# Control.net
KiCad netlist of a schematic drawn in EAGLE
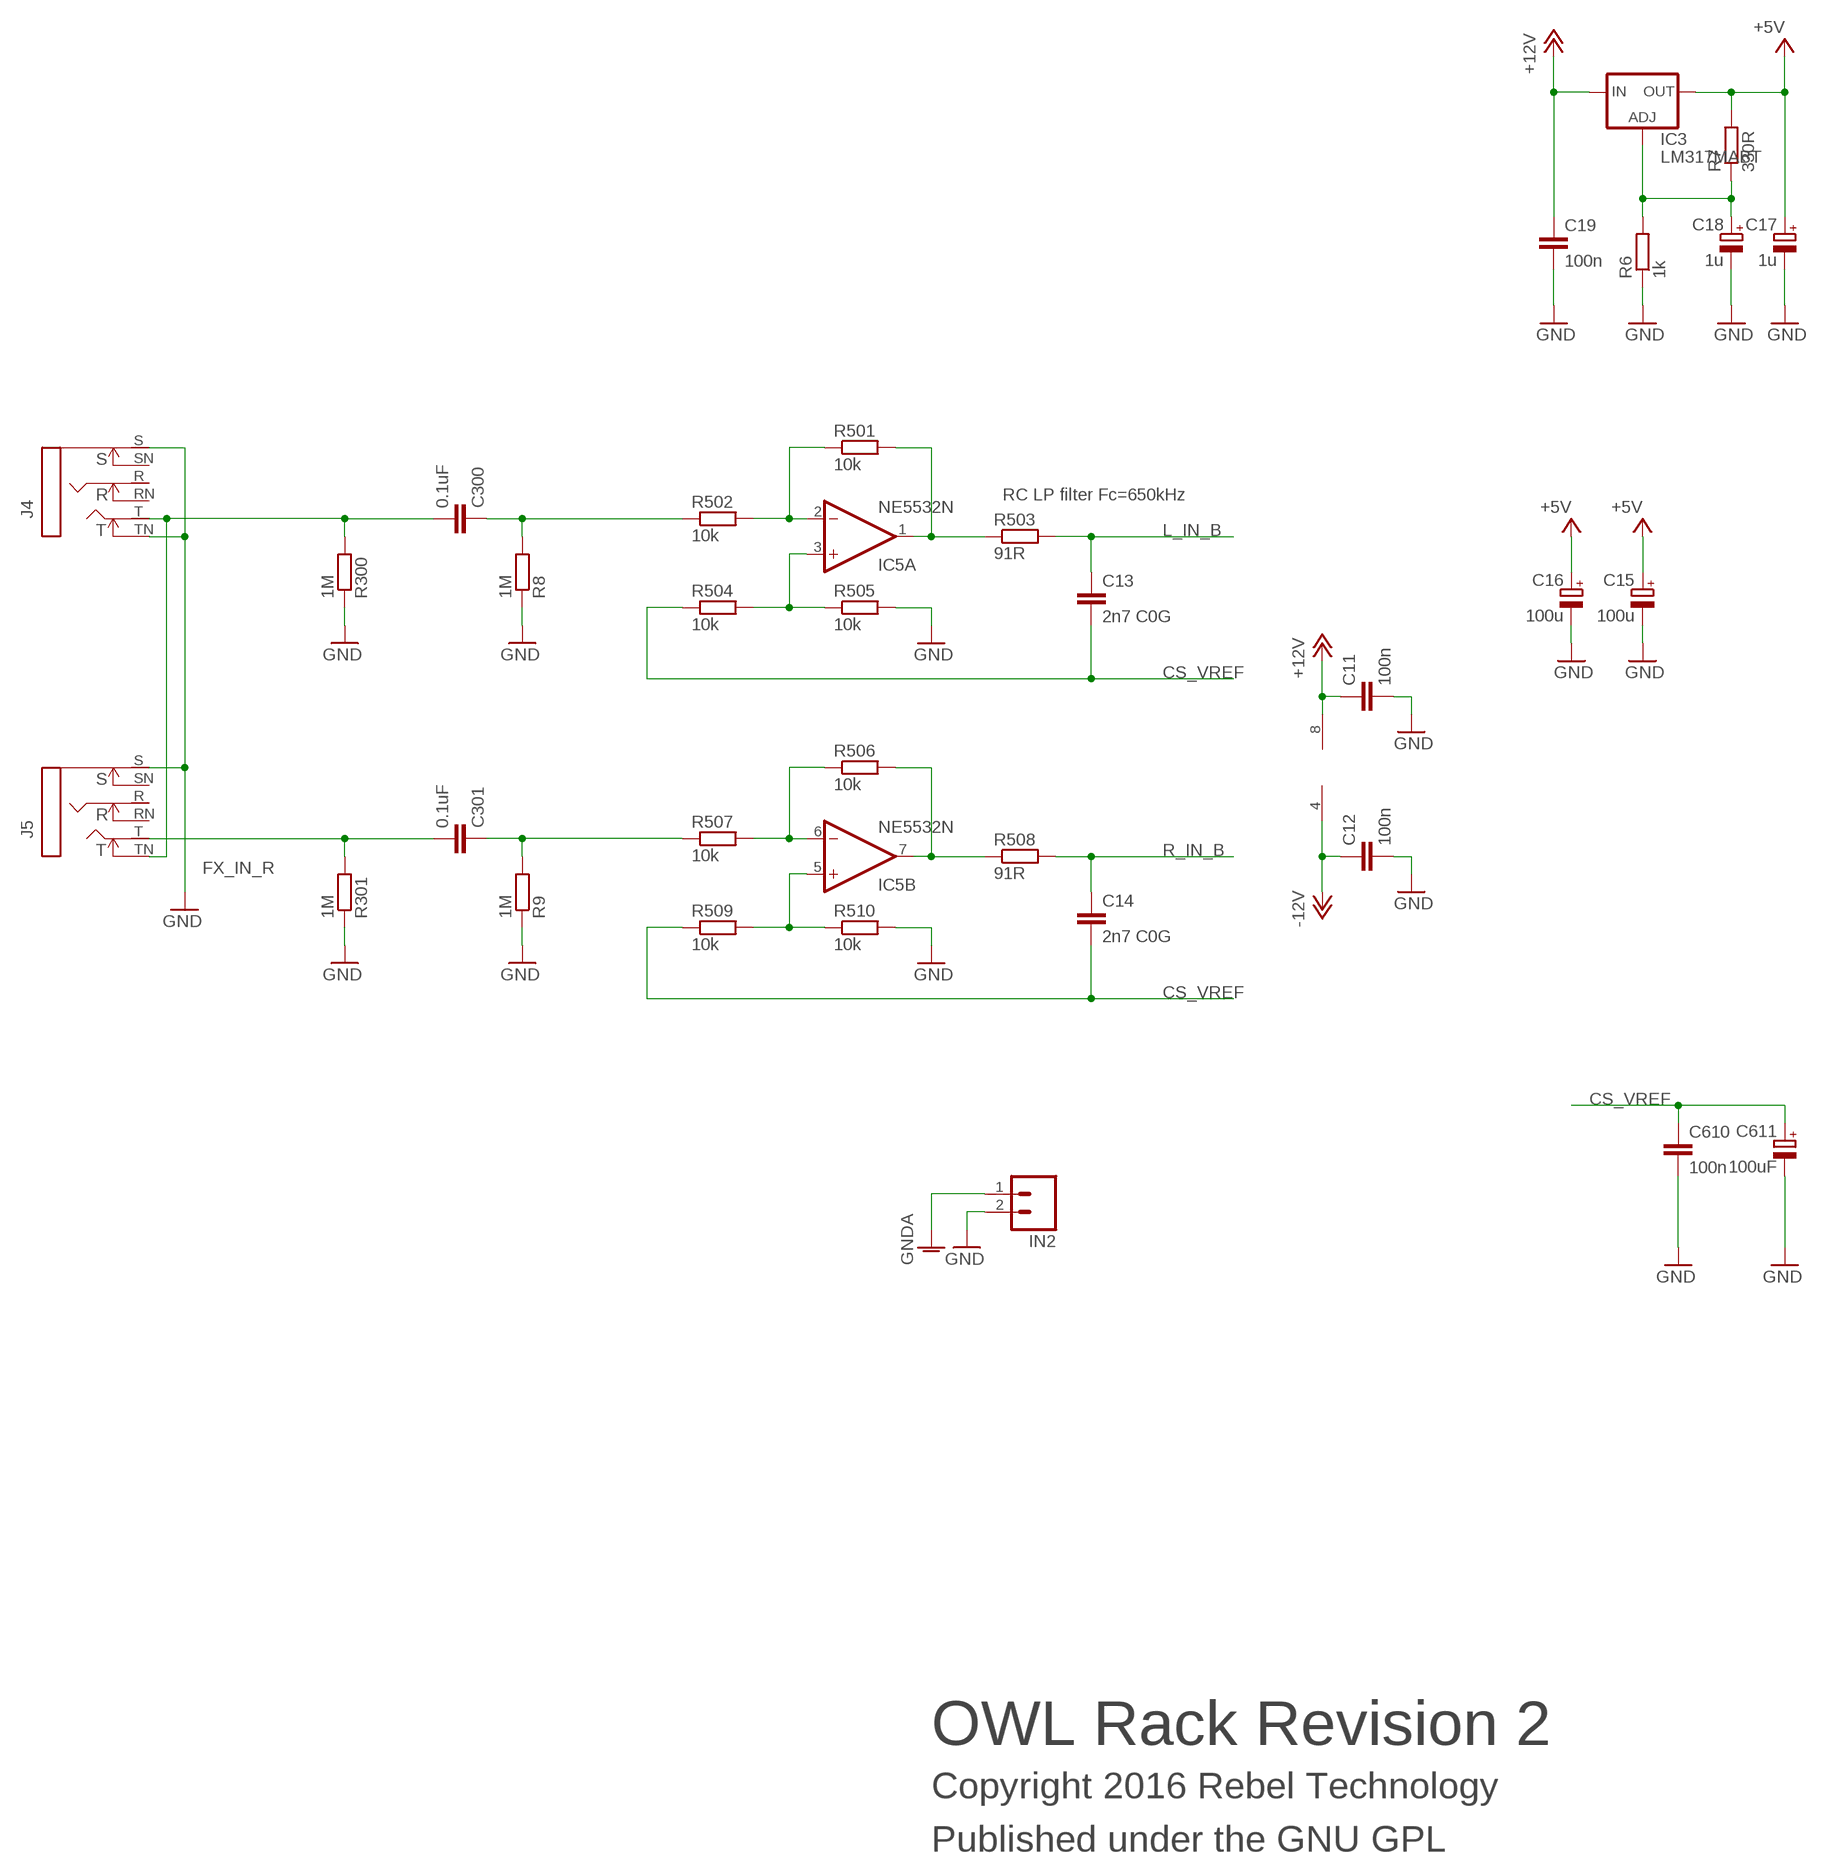
[diagram p0: schematic, sheet 1, part 1 of 2]
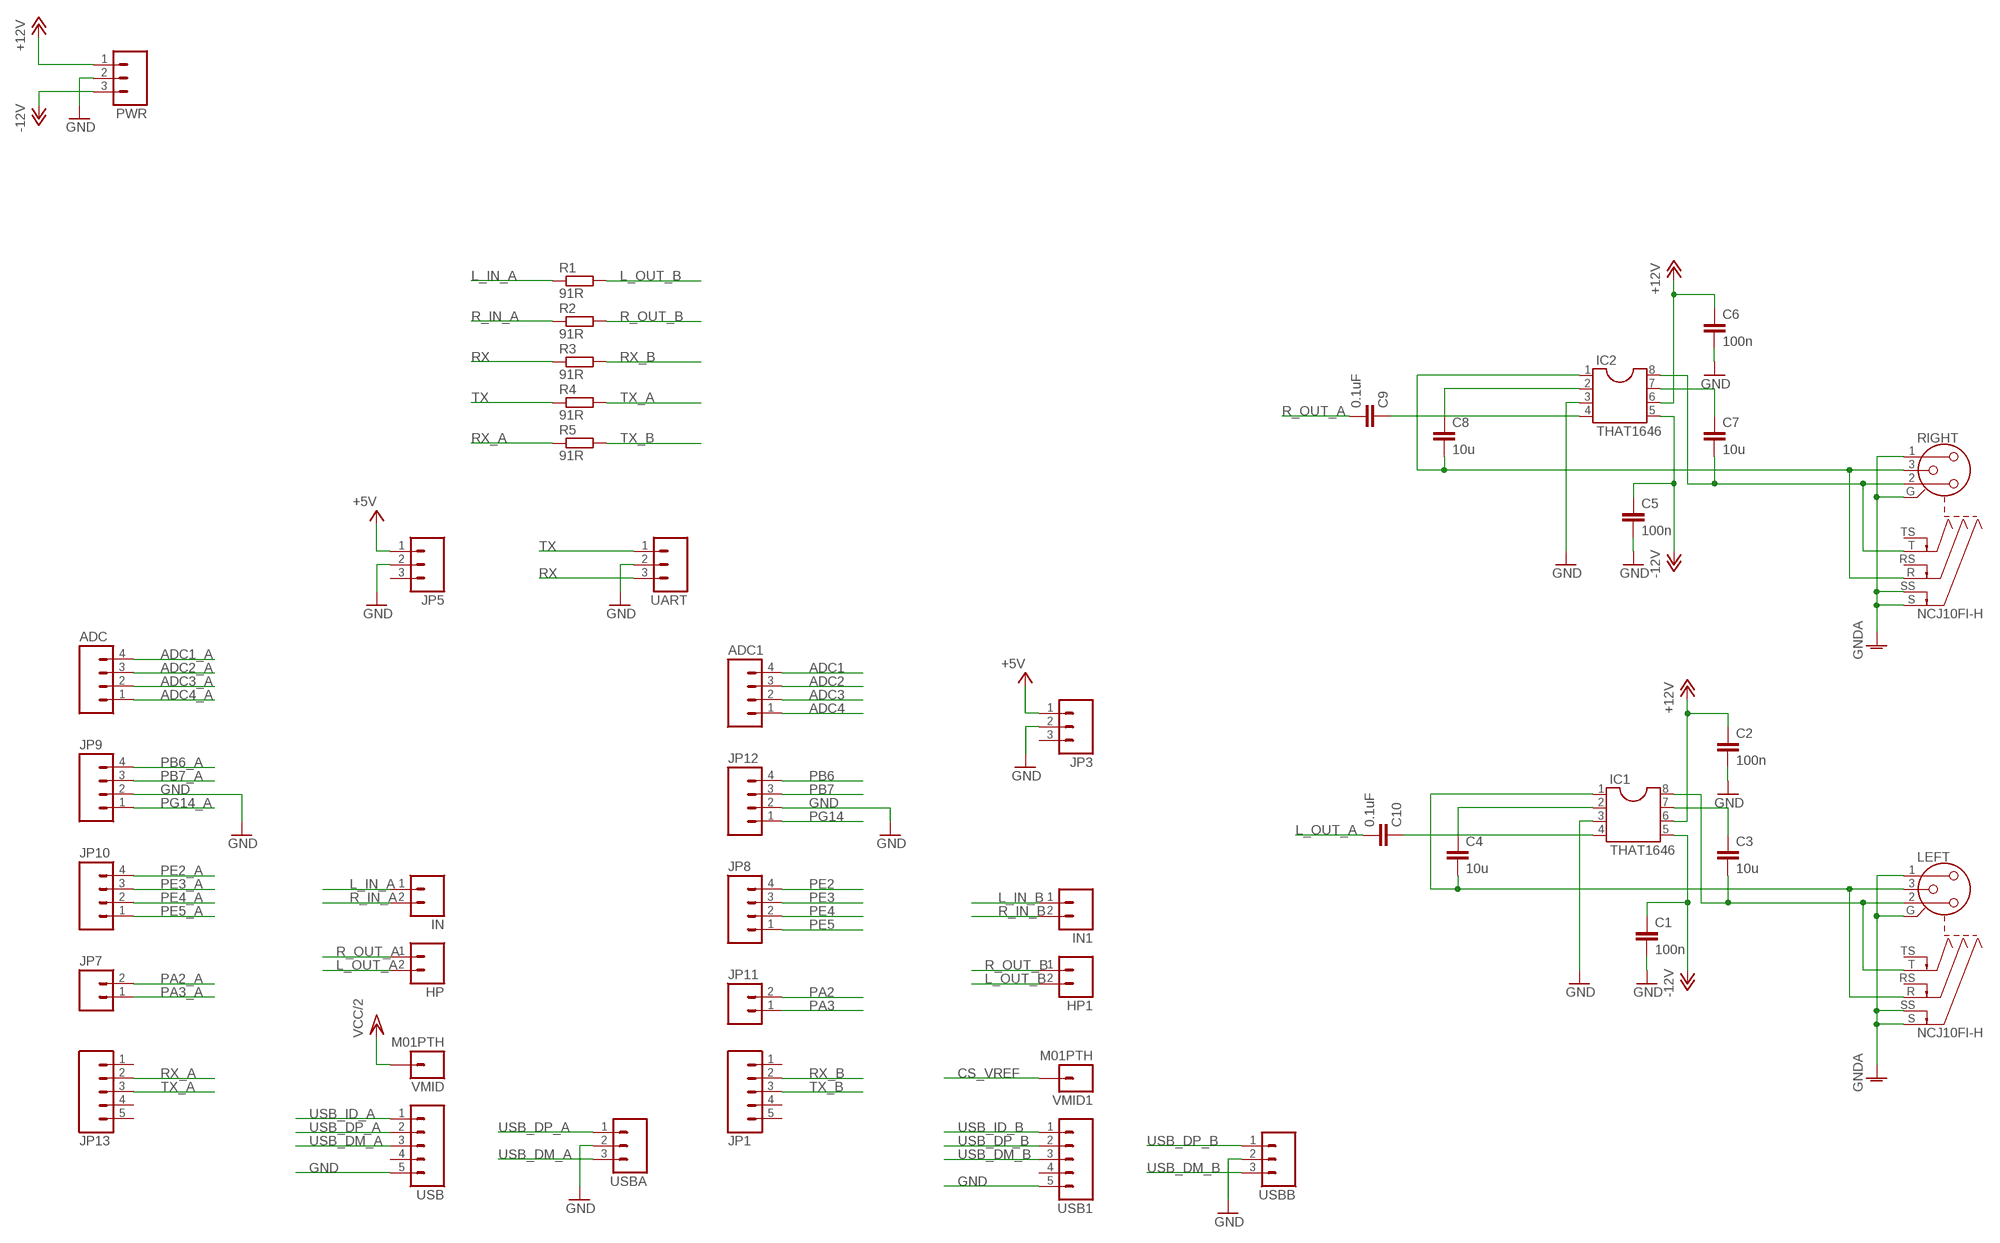
[diagram p1: schematic, sheet 1, part 2 of 2]

(export (version "E")
  (design (tool "Eeschema 10.0.6"))
  (components
    (comp (ref "ADC")
      (value "M04PTH")
      (footprint "eagle-import:1X04")
      (libsource (lib "eagle-import") (part "M04PTH"))
    )
    (comp (ref "ADC1")
      (value "M04PTH")
      (footprint "eagle-import:1X04")
      (libsource (lib "eagle-import") (part "M04PTH"))
    )
    (comp (ref "C1")
      (value "100n")
      (footprint "eagle-import:C050-025X075")
      (libsource (lib "eagle-import") (part "C-EU050-025X075"))
    )
    (comp (ref "C2")
      (value "100n")
      (footprint "eagle-import:C050-025X075")
      (libsource (lib "eagle-import") (part "C-EU050-025X075"))
    )
    (comp (ref "C3")
      (value "10u")
      (footprint "eagle-import:C050-025X075")
      (libsource (lib "eagle-import") (part "C-EU050-025X075"))
    )
    (comp (ref "C4")
      (value "10u")
      (footprint "eagle-import:C050-025X075")
      (libsource (lib "eagle-import") (part "C-EU050-025X075"))
    )
    (comp (ref "C5")
      (value "100n")
      (footprint "eagle-import:C050-025X075")
      (libsource (lib "eagle-import") (part "C-EU050-025X075"))
    )
    (comp (ref "C6")
      (value "100n")
      (footprint "eagle-import:C050-025X075")
      (libsource (lib "eagle-import") (part "C-EU050-025X075"))
    )
    (comp (ref "C7")
      (value "10u")
      (footprint "eagle-import:C050-025X075")
      (libsource (lib "eagle-import") (part "C-EU050-025X075"))
    )
    (comp (ref "C8")
      (value "10u")
      (footprint "eagle-import:C050-025X075")
      (libsource (lib "eagle-import") (part "C-EU050-025X075"))
    )
    (comp (ref "C9")
      (value "0.1uF")
      (footprint "eagle-import:C5B3.5")
      (libsource (lib "eagle-import") (part "C5/3.5"))
    )
    (comp (ref "C10")
      (value "0.1uF")
      (footprint "eagle-import:C5B3.5")
      (libsource (lib "eagle-import") (part "C5/3.5"))
    )
    (comp (ref "C11")
      (value "100n")
      (footprint "eagle-import:C050-025X075")
      (libsource (lib "eagle-import") (part "C-EU050-025X075"))
    )
    (comp (ref "C12")
      (value "100n")
      (footprint "eagle-import:C050-025X075")
      (libsource (lib "eagle-import") (part "C-EU050-025X075"))
    )
    (comp (ref "C13")
      (value "2n7 C0G")
      (footprint "eagle-import:C050-025X075")
      (libsource (lib "eagle-import") (part "C-EU050-025X075"))
    )
    (comp (ref "C14")
      (value "2n7 C0G")
      (footprint "eagle-import:C050-025X075")
      (libsource (lib "eagle-import") (part "C-EU050-025X075"))
    )
    (comp (ref "C15")
      (value "100u")
      (footprint "eagle-import:E2,5-7")
      (libsource (lib "eagle-import") (part "CPOL-EUE2.5-7"))
    )
    (comp (ref "C16")
      (value "100u")
      (footprint "eagle-import:E2,5-7")
      (libsource (lib "eagle-import") (part "CPOL-EUE2.5-7"))
    )
    (comp (ref "C17")
      (value "1u")
      (footprint "eagle-import:E2,5-7")
      (libsource (lib "eagle-import") (part "CPOL-EUE2.5-7"))
    )
    (comp (ref "C18")
      (value "1u")
      (footprint "eagle-import:E2,5-7")
      (libsource (lib "eagle-import") (part "CPOL-EUE2.5-7"))
    )
    (comp (ref "C19")
      (value "100n")
      (footprint "eagle-import:C050-025X075")
      (libsource (lib "eagle-import") (part "C-EU050-025X075"))
    )
    (comp (ref "C300")
      (value "0.1uF")
      (footprint "eagle-import:C5B3.5")
      (libsource (lib "eagle-import") (part "C5/3.5"))
    )
    (comp (ref "C301")
      (value "0.1uF")
      (footprint "eagle-import:C5B3.5")
      (libsource (lib "eagle-import") (part "C5/3.5"))
    )
    (comp (ref "C610")
      (value "100n")
      (footprint "eagle-import:C050-025X075")
      (libsource (lib "eagle-import") (part "C-EU050-025X075"))
    )
    (comp (ref "C611")
      (value "100uF")
      (footprint "eagle-import:E2,5-7")
      (libsource (lib "eagle-import") (part "CPOL-EUE2.5-7"))
    )
    (comp (ref "HP")
      (value "M02PTH")
      (footprint "eagle-import:1X02")
      (libsource (lib "eagle-import") (part "M02PTH"))
    )
    (comp (ref "HP1")
      (value "M02PTH")
      (footprint "eagle-import:1X02")
      (libsource (lib "eagle-import") (part "M02PTH"))
    )
    (comp (ref "IC1")
      (value "THAT1646")
      (footprint "eagle-import:DIL08")
      (libsource (lib "eagle-import") (part "DIL8"))
    )
    (comp (ref "IC2")
      (value "THAT1646")
      (footprint "eagle-import:DIL08")
      (libsource (lib "eagle-import") (part "DIL8"))
    )
    (comp (ref "IC3")
      (value "LM317MABT")
      (footprint "eagle-import:TO220L1")
      (libsource (lib "eagle-import") (part "LM317?MABT"))
    )
    (comp (ref "IC5")
      (value "NE5532N")
      (footprint "eagle-import:DIL08")
      (libsource (lib "eagle-import") (part "NE5532N"))
    )
    (comp (ref "IN")
      (value "M02PTH")
      (footprint "eagle-import:1X02")
      (libsource (lib "eagle-import") (part "M02PTH"))
    )
    (comp (ref "IN1")
      (value "M02PTH")
      (footprint "eagle-import:1X02")
      (libsource (lib "eagle-import") (part "M02PTH"))
    )
    (comp (ref "IN2")
      (value "M02PTH")
      (footprint "eagle-import:1X02")
      (libsource (lib "eagle-import") (part "M02PTH"))
    )
    (comp (ref "J4")
      (value "NEUTRIK_NMJ6HCD2")
      (footprint "eagle-import:NMJ6HCD2")
      (libsource (lib "eagle-import") (part "NEUTRIK_NMJ6HCD2"))
    )
    (comp (ref "J5")
      (value "NEUTRIK_NMJ6HCD2")
      (footprint "eagle-import:NMJ6HCD2")
      (libsource (lib "eagle-import") (part "NEUTRIK_NMJ6HCD2"))
    )
    (comp (ref "JP1")
      (value "M05PTH")
      (footprint "eagle-import:1X05")
      (libsource (lib "eagle-import") (part "M05PTH"))
    )
    (comp (ref "JP3")
      (value "M03PTH")
      (footprint "eagle-import:1X03")
      (libsource (lib "eagle-import") (part "M03PTH"))
    )
    (comp (ref "JP5")
      (value "M03PTH")
      (footprint "eagle-import:1X03")
      (libsource (lib "eagle-import") (part "M03PTH"))
    )
    (comp (ref "JP7")
      (value "M02PTH")
      (footprint "eagle-import:1X02")
      (libsource (lib "eagle-import") (part "M02PTH"))
    )
    (comp (ref "JP8")
      (value "M04PTH")
      (footprint "eagle-import:1X04")
      (libsource (lib "eagle-import") (part "M04PTH"))
    )
    (comp (ref "JP9")
      (value "M04PTH")
      (footprint "eagle-import:1X04")
      (libsource (lib "eagle-import") (part "M04PTH"))
    )
    (comp (ref "JP10")
      (value "M04PTH")
      (footprint "eagle-import:1X04")
      (libsource (lib "eagle-import") (part "M04PTH"))
    )
    (comp (ref "JP11")
      (value "M02PTH")
      (footprint "eagle-import:1X02")
      (libsource (lib "eagle-import") (part "M02PTH"))
    )
    (comp (ref "JP12")
      (value "M04PTH")
      (footprint "eagle-import:1X04")
      (libsource (lib "eagle-import") (part "M04PTH"))
    )
    (comp (ref "JP13")
      (value "M05PTH")
      (footprint "eagle-import:1X05")
      (libsource (lib "eagle-import") (part "M05PTH"))
    )
    (comp (ref "LEFT")
      (value "NCJ10FI-H")
      (footprint "eagle-import:NCJ10FI-H")
      (libsource (lib "eagle-import") (part "NCJ10FI-H"))
    )
    (comp (ref "PWR")
      (value "M03PTH")
      (footprint "eagle-import:1X03")
      (libsource (lib "eagle-import") (part "M03PTH"))
    )
    (comp (ref "R1")
      (value "91R")
      (footprint "eagle-import:0204_7")
      (libsource (lib "eagle-import") (part "R-EU_0204/7"))
    )
    (comp (ref "R2")
      (value "91R")
      (footprint "eagle-import:0204_7")
      (libsource (lib "eagle-import") (part "R-EU_0204/7"))
    )
    (comp (ref "R3")
      (value "91R")
      (footprint "eagle-import:0204_7")
      (libsource (lib "eagle-import") (part "R-EU_0204/7"))
    )
    (comp (ref "R4")
      (value "91R")
      (footprint "eagle-import:0204_7")
      (libsource (lib "eagle-import") (part "R-EU_0204/7"))
    )
    (comp (ref "R5")
      (value "91R")
      (footprint "eagle-import:0204_7")
      (libsource (lib "eagle-import") (part "R-EU_0204/7"))
    )
    (comp (ref "R6")
      (value "1k")
      (footprint "eagle-import:0204_7")
      (libsource (lib "eagle-import") (part "R-EU_0204/7"))
    )
    (comp (ref "R7")
      (value "330R")
      (footprint "eagle-import:0204_7")
      (libsource (lib "eagle-import") (part "R-EU_0204/7"))
    )
    (comp (ref "R8")
      (value "1M")
      (footprint "eagle-import:0204_7")
      (libsource (lib "eagle-import") (part "R-EU_0204/7"))
    )
    (comp (ref "R9")
      (value "1M")
      (footprint "eagle-import:0204_7")
      (libsource (lib "eagle-import") (part "R-EU_0204/7"))
    )
    (comp (ref "R300")
      (value "1M")
      (footprint "eagle-import:0204_7")
      (libsource (lib "eagle-import") (part "R-EU_0204/7"))
    )
    (comp (ref "R301")
      (value "1M")
      (footprint "eagle-import:0204_7")
      (libsource (lib "eagle-import") (part "R-EU_0204/7"))
    )
    (comp (ref "R501")
      (value "10k")
      (footprint "eagle-import:0204_7")
      (libsource (lib "eagle-import") (part "R-EU_0204/7"))
    )
    (comp (ref "R502")
      (value "10k")
      (footprint "eagle-import:0204_7")
      (libsource (lib "eagle-import") (part "R-EU_0204/7"))
    )
    (comp (ref "R503")
      (value "91R")
      (footprint "eagle-import:0204_7")
      (libsource (lib "eagle-import") (part "R-EU_0204/7"))
    )
    (comp (ref "R504")
      (value "10k")
      (footprint "eagle-import:0204_7")
      (libsource (lib "eagle-import") (part "R-EU_0204/7"))
    )
    (comp (ref "R505")
      (value "10k")
      (footprint "eagle-import:0204_7")
      (libsource (lib "eagle-import") (part "R-EU_0204/7"))
    )
    (comp (ref "R506")
      (value "10k")
      (footprint "eagle-import:0204_7")
      (libsource (lib "eagle-import") (part "R-EU_0204/7"))
    )
    (comp (ref "R507")
      (value "10k")
      (footprint "eagle-import:0204_7")
      (libsource (lib "eagle-import") (part "R-EU_0204/7"))
    )
    (comp (ref "R508")
      (value "91R")
      (footprint "eagle-import:0204_7")
      (libsource (lib "eagle-import") (part "R-EU_0204/7"))
    )
    (comp (ref "R509")
      (value "10k")
      (footprint "eagle-import:0204_7")
      (libsource (lib "eagle-import") (part "R-EU_0204/7"))
    )
    (comp (ref "R510")
      (value "10k")
      (footprint "eagle-import:0204_7")
      (libsource (lib "eagle-import") (part "R-EU_0204/7"))
    )
    (comp (ref "RIGHT")
      (value "NCJ10FI-H")
      (footprint "eagle-import:NCJ10FI-H")
      (libsource (lib "eagle-import") (part "NCJ10FI-H"))
    )
    (comp (ref "UART")
      (value "M03PTH")
      (footprint "eagle-import:1X03")
      (libsource (lib "eagle-import") (part "M03PTH"))
    )
    (comp (ref "USB")
      (value "M05PTH")
      (footprint "eagle-import:1X05")
      (libsource (lib "eagle-import") (part "M05PTH"))
    )
    (comp (ref "USB1")
      (value "M05PTH")
      (footprint "eagle-import:1X05")
      (libsource (lib "eagle-import") (part "M05PTH"))
    )
    (comp (ref "USBA")
      (value "M03PTH")
      (footprint "eagle-import:1X03")
      (libsource (lib "eagle-import") (part "M03PTH"))
    )
    (comp (ref "USBB")
      (value "M03PTH")
      (footprint "eagle-import:1X03")
      (libsource (lib "eagle-import") (part "M03PTH"))
    )
    (comp (ref "VMID")
      (value "M01PTH")
      (footprint "eagle-import:1X01")
      (libsource (lib "eagle-import") (part "M01PTH"))
    )
    (comp (ref "VMID1")
      (value "M01PTH")
      (footprint "eagle-import:1X01")
      (libsource (lib "eagle-import") (part "M01PTH"))
    )
  )
  (nets
    (net (code "1") (name "+5V") (class "Default")
      (node (ref "C15") (pin "+") (pinfunction "+_+") (pintype "passive"))
      (node (ref "C16") (pin "+") (pinfunction "+_+") (pintype "passive"))
      (node (ref "C17") (pin "+") (pinfunction "+_+") (pintype "passive"))
      (node (ref "IC3") (pin "2") (pinfunction "OUT_2") (pintype "passive"))
      (node (ref "JP3") (pin "1") (pinfunction "1_1") (pintype "passive"))
      (node (ref "JP5") (pin "1") (pinfunction "1_1") (pintype "passive"))
      (node (ref "R7") (pin "2") (pinfunction "2_2") (pintype "passive"))
    )
    (net (code "2") (name "+12V") (class "Default")
      (node (ref "C11") (pin "1") (pinfunction "1_1") (pintype "passive"))
      (node (ref "C19") (pin "1") (pinfunction "1_1") (pintype "passive"))
      (node (ref "C2") (pin "1") (pinfunction "1_1") (pintype "passive"))
      (node (ref "C6") (pin "1") (pinfunction "1_1") (pintype "passive"))
      (node (ref "IC1") (pin "6") (pinfunction "6_6") (pintype "passive"))
      (node (ref "IC2") (pin "6") (pinfunction "6_6") (pintype "passive"))
      (node (ref "IC3") (pin "3") (pinfunction "IN_3") (pintype "input"))
      (node (ref "IC5") (pin "8") (pinfunction "V+_8") (pintype "power_in"))
      (node (ref "PWR") (pin "1") (pinfunction "1_1") (pintype "passive"))
    )
    (net (code "3") (name "-12V") (class "Default")
      (node (ref "C1") (pin "1") (pinfunction "1_1") (pintype "passive"))
      (node (ref "C12") (pin "1") (pinfunction "1_1") (pintype "passive"))
      (node (ref "C5") (pin "1") (pinfunction "1_1") (pintype "passive"))
      (node (ref "IC1") (pin "5") (pinfunction "5_5") (pintype "passive"))
      (node (ref "IC2") (pin "5") (pinfunction "5_5") (pintype "passive"))
      (node (ref "IC5") (pin "4") (pinfunction "V-_4") (pintype "power_in"))
      (node (ref "PWR") (pin "3") (pinfunction "3_3") (pintype "passive"))
    )
    (net (code "4") (name "/ADC1") (class "Default")
      (node (ref "ADC1") (pin "4") (pinfunction "4_4") (pintype "passive"))
    )
    (net (code "5") (name "/ADC1_A") (class "Default")
      (node (ref "ADC") (pin "4") (pinfunction "4_4") (pintype "passive"))
    )
    (net (code "6") (name "/ADC2") (class "Default")
      (node (ref "ADC1") (pin "3") (pinfunction "3_3") (pintype "passive"))
    )
    (net (code "7") (name "/ADC2_A") (class "Default")
      (node (ref "ADC") (pin "3") (pinfunction "3_3") (pintype "passive"))
    )
    (net (code "8") (name "/ADC3") (class "Default")
      (node (ref "ADC1") (pin "2") (pinfunction "2_2") (pintype "passive"))
    )
    (net (code "9") (name "/ADC3_A") (class "Default")
      (node (ref "ADC") (pin "2") (pinfunction "2_2") (pintype "passive"))
    )
    (net (code "10") (name "/ADC4") (class "Default")
      (node (ref "ADC1") (pin "1") (pinfunction "1_1") (pintype "passive"))
    )
    (net (code "11") (name "/ADC4_A") (class "Default")
      (node (ref "ADC") (pin "1") (pinfunction "1_1") (pintype "passive"))
    )
    (net (code "12") (name "/CS_VREF") (class "Default")
      (node (ref "C13") (pin "2") (pinfunction "2_2") (pintype "passive"))
      (node (ref "C14") (pin "2") (pinfunction "2_2") (pintype "passive"))
      (node (ref "C610") (pin "1") (pinfunction "1_1") (pintype "passive"))
      (node (ref "C611") (pin "+") (pinfunction "+_+") (pintype "passive"))
      (node (ref "R504") (pin "1") (pinfunction "1_1") (pintype "passive"))
      (node (ref "R509") (pin "1") (pinfunction "1_1") (pintype "passive"))
      (node (ref "VMID1") (pin "1") (pinfunction "1_1") (pintype "passive"))
    )
    (net (code "13") (name "/FX_IN_R") (class "Default")
      (node (ref "C301") (pin "2") (pinfunction "2_2") (pintype "passive"))
      (node (ref "J5") (pin "T") (pinfunction "T_T") (pintype "passive"))
      (node (ref "R301") (pin "2") (pinfunction "2_2") (pintype "passive"))
    )
    (net (code "14") (name "/L_IN_A") (class "Default")
      (node (ref "IN") (pin "1") (pinfunction "1_1") (pintype "passive"))
      (node (ref "R1") (pin "1") (pinfunction "1_1") (pintype "passive"))
    )
    (net (code "15") (name "/L_IN_B") (class "Default")
      (node (ref "C13") (pin "1") (pinfunction "1_1") (pintype "passive"))
      (node (ref "IN1") (pin "1") (pinfunction "1_1") (pintype "passive"))
      (node (ref "R503") (pin "2") (pinfunction "2_2") (pintype "passive"))
    )
    (net (code "16") (name "/L_OUT_A") (class "Default")
      (node (ref "C10") (pin "2") (pinfunction "2_2") (pintype "passive"))
      (node (ref "HP") (pin "2") (pinfunction "2_2") (pintype "passive"))
    )
    (net (code "17") (name "/L_OUT_B") (class "Default")
      (node (ref "HP1") (pin "2") (pinfunction "2_2") (pintype "passive"))
      (node (ref "R1") (pin "2") (pinfunction "2_2") (pintype "passive"))
    )
    (net (code "18") (name "/PA2") (class "Default")
      (node (ref "JP11") (pin "2") (pinfunction "2_2") (pintype "passive"))
    )
    (net (code "19") (name "/PA2_A") (class "Default")
      (node (ref "JP7") (pin "2") (pinfunction "2_2") (pintype "passive"))
    )
    (net (code "20") (name "/PA3") (class "Default")
      (node (ref "JP11") (pin "1") (pinfunction "1_1") (pintype "passive"))
    )
    (net (code "21") (name "/PA3_A") (class "Default")
      (node (ref "JP7") (pin "1") (pinfunction "1_1") (pintype "passive"))
    )
    (net (code "22") (name "/PB6") (class "Default")
      (node (ref "JP12") (pin "4") (pinfunction "4_4") (pintype "passive"))
    )
    (net (code "23") (name "/PB6_A") (class "Default")
      (node (ref "JP9") (pin "4") (pinfunction "4_4") (pintype "passive"))
    )
    (net (code "24") (name "/PB7") (class "Default")
      (node (ref "JP12") (pin "3") (pinfunction "3_3") (pintype "passive"))
    )
    (net (code "25") (name "/PB7_A") (class "Default")
      (node (ref "JP9") (pin "3") (pinfunction "3_3") (pintype "passive"))
    )
    (net (code "26") (name "/PE2") (class "Default")
      (node (ref "JP8") (pin "4") (pinfunction "4_4") (pintype "passive"))
    )
    (net (code "27") (name "/PE2_A") (class "Default")
      (node (ref "JP10") (pin "4") (pinfunction "4_4") (pintype "passive"))
    )
    (net (code "28") (name "/PE3") (class "Default")
      (node (ref "JP8") (pin "3") (pinfunction "3_3") (pintype "passive"))
    )
    (net (code "29") (name "/PE3_A") (class "Default")
      (node (ref "JP10") (pin "3") (pinfunction "3_3") (pintype "passive"))
    )
    (net (code "30") (name "/PE4") (class "Default")
      (node (ref "JP8") (pin "2") (pinfunction "2_2") (pintype "passive"))
    )
    (net (code "31") (name "/PE4_A") (class "Default")
      (node (ref "JP10") (pin "2") (pinfunction "2_2") (pintype "passive"))
    )
    (net (code "32") (name "/PE5") (class "Default")
      (node (ref "JP8") (pin "1") (pinfunction "1_1") (pintype "passive"))
    )
    (net (code "33") (name "/PE5_A") (class "Default")
      (node (ref "JP10") (pin "1") (pinfunction "1_1") (pintype "passive"))
    )
    (net (code "34") (name "/PG14") (class "Default")
      (node (ref "JP12") (pin "1") (pinfunction "1_1") (pintype "passive"))
    )
    (net (code "35") (name "/PG14_A") (class "Default")
      (node (ref "JP9") (pin "1") (pinfunction "1_1") (pintype "passive"))
    )
    (net (code "36") (name "/RX") (class "Default")
      (node (ref "R3") (pin "1") (pinfunction "1_1") (pintype "passive"))
      (node (ref "UART") (pin "3") (pinfunction "3_3") (pintype "passive"))
    )
    (net (code "37") (name "/RX_A") (class "Default")
      (node (ref "JP13") (pin "2") (pinfunction "2_2") (pintype "passive"))
      (node (ref "R5") (pin "1") (pinfunction "1_1") (pintype "passive"))
    )
    (net (code "38") (name "/RX_B") (class "Default")
      (node (ref "JP1") (pin "2") (pinfunction "2_2") (pintype "passive"))
      (node (ref "R3") (pin "2") (pinfunction "2_2") (pintype "passive"))
    )
    (net (code "39") (name "/R_IN_A") (class "Default")
      (node (ref "IN") (pin "2") (pinfunction "2_2") (pintype "passive"))
      (node (ref "R2") (pin "1") (pinfunction "1_1") (pintype "passive"))
    )
    (net (code "40") (name "/R_IN_B") (class "Default")
      (node (ref "C14") (pin "1") (pinfunction "1_1") (pintype "passive"))
      (node (ref "IN1") (pin "2") (pinfunction "2_2") (pintype "passive"))
      (node (ref "R508") (pin "2") (pinfunction "2_2") (pintype "passive"))
    )
    (net (code "41") (name "/R_OUT_A") (class "Default")
      (node (ref "C9") (pin "2") (pinfunction "2_2") (pintype "passive"))
      (node (ref "HP") (pin "1") (pinfunction "1_1") (pintype "passive"))
    )
    (net (code "42") (name "/R_OUT_B") (class "Default")
      (node (ref "HP1") (pin "1") (pinfunction "1_1") (pintype "passive"))
      (node (ref "R2") (pin "2") (pinfunction "2_2") (pintype "passive"))
    )
    (net (code "43") (name "/TX") (class "Default")
      (node (ref "R4") (pin "1") (pinfunction "1_1") (pintype "passive"))
      (node (ref "UART") (pin "1") (pinfunction "1_1") (pintype "passive"))
    )
    (net (code "44") (name "/TX_A") (class "Default")
      (node (ref "JP13") (pin "3") (pinfunction "3_3") (pintype "passive"))
      (node (ref "R4") (pin "2") (pinfunction "2_2") (pintype "passive"))
    )
    (net (code "45") (name "/TX_B") (class "Default")
      (node (ref "JP1") (pin "3") (pinfunction "3_3") (pintype "passive"))
      (node (ref "R5") (pin "2") (pinfunction "2_2") (pintype "passive"))
    )
    (net (code "46") (name "/USB_DM_A") (class "Default")
      (node (ref "USB") (pin "3") (pinfunction "3_3") (pintype "passive"))
      (node (ref "USBA") (pin "3") (pinfunction "3_3") (pintype "passive"))
    )
    (net (code "47") (name "/USB_DM_B") (class "Default")
      (node (ref "USB1") (pin "3") (pinfunction "3_3") (pintype "passive"))
      (node (ref "USBB") (pin "3") (pinfunction "3_3") (pintype "passive"))
    )
    (net (code "48") (name "/USB_DP_A") (class "Default")
      (node (ref "USB") (pin "2") (pinfunction "2_2") (pintype "passive"))
      (node (ref "USBA") (pin "1") (pinfunction "1_1") (pintype "passive"))
    )
    (net (code "49") (name "/USB_DP_B") (class "Default")
      (node (ref "USB1") (pin "2") (pinfunction "2_2") (pintype "passive"))
      (node (ref "USBB") (pin "1") (pinfunction "1_1") (pintype "passive"))
    )
    (net (code "50") (name "/USB_ID_A") (class "Default")
      (node (ref "USB") (pin "1") (pinfunction "1_1") (pintype "passive"))
    )
    (net (code "51") (name "/USB_ID_B") (class "Default")
      (node (ref "USB1") (pin "1") (pinfunction "1_1") (pintype "passive"))
    )
    (net (code "52") (name "GND") (class "Default")
      (node (ref "C1") (pin "2") (pinfunction "2_2") (pintype "passive"))
      (node (ref "C11") (pin "2") (pinfunction "2_2") (pintype "passive"))
      (node (ref "C12") (pin "2") (pinfunction "2_2") (pintype "passive"))
      (node (ref "C15") (pin "-") (pinfunction "-_-") (pintype "passive"))
      (node (ref "C16") (pin "-") (pinfunction "-_-") (pintype "passive"))
      (node (ref "C17") (pin "-") (pinfunction "-_-") (pintype "passive"))
      (node (ref "C18") (pin "-") (pinfunction "-_-") (pintype "passive"))
      (node (ref "C19") (pin "2") (pinfunction "2_2") (pintype "passive"))
      (node (ref "C2") (pin "2") (pinfunction "2_2") (pintype "passive"))
      (node (ref "C5") (pin "2") (pinfunction "2_2") (pintype "passive"))
      (node (ref "C6") (pin "2") (pinfunction "2_2") (pintype "passive"))
      (node (ref "C610") (pin "2") (pinfunction "2_2") (pintype "passive"))
      (node (ref "C611") (pin "-") (pinfunction "-_-") (pintype "passive"))
      (node (ref "IC1") (pin "3") (pinfunction "3_3") (pintype "passive"))
      (node (ref "IC2") (pin "3") (pinfunction "3_3") (pintype "passive"))
      (node (ref "IN2") (pin "2") (pinfunction "2_2") (pintype "passive"))
      (node (ref "J4") (pin "S") (pinfunction "S_S") (pintype "passive"))
      (node (ref "J4") (pin "TN") (pinfunction "TN_TN") (pintype "passive"))
      (node (ref "J5") (pin "S") (pinfunction "S_S") (pintype "passive"))
      (node (ref "JP12") (pin "2") (pinfunction "2_2") (pintype "passive"))
      (node (ref "JP3") (pin "2") (pinfunction "2_2") (pintype "passive"))
      (node (ref "JP5") (pin "2") (pinfunction "2_2") (pintype "passive"))
      (node (ref "JP9") (pin "2") (pinfunction "2_2") (pintype "passive"))
      (node (ref "PWR") (pin "2") (pinfunction "2_2") (pintype "passive"))
      (node (ref "R300") (pin "1") (pinfunction "1_1") (pintype "passive"))
      (node (ref "R301") (pin "1") (pinfunction "1_1") (pintype "passive"))
      (node (ref "R505") (pin "2") (pinfunction "2_2") (pintype "passive"))
      (node (ref "R510") (pin "2") (pinfunction "2_2") (pintype "passive"))
      (node (ref "R6") (pin "1") (pinfunction "1_1") (pintype "passive"))
      (node (ref "R8") (pin "1") (pinfunction "1_1") (pintype "passive"))
      (node (ref "R9") (pin "1") (pinfunction "1_1") (pintype "passive"))
      (node (ref "UART") (pin "2") (pinfunction "2_2") (pintype "passive"))
      (node (ref "USB") (pin "5") (pinfunction "5_5") (pintype "passive"))
      (node (ref "USB1") (pin "5") (pinfunction "5_5") (pintype "passive"))
      (node (ref "USBA") (pin "2") (pinfunction "2_2") (pintype "passive"))
      (node (ref "USBB") (pin "2") (pinfunction "2_2") (pintype "passive"))
    )
    (net (code "53") (name "GNDA") (class "Default")
      (node (ref "IN2") (pin "1") (pinfunction "1_1") (pintype "passive"))
      (node (ref "LEFT") (pin "1") (pinfunction "1_1") (pintype "passive"))
      (node (ref "LEFT") (pin "G") (pinfunction "G_G") (pintype "passive"))
      (node (ref "LEFT") (pin "S") (pinfunction "S_S") (pintype "passive"))
      (node (ref "LEFT") (pin "SS") (pinfunction "SS_SS") (pintype "passive"))
      (node (ref "RIGHT") (pin "1") (pinfunction "1_1") (pintype "passive"))
      (node (ref "RIGHT") (pin "G") (pinfunction "G_G") (pintype "passive"))
      (node (ref "RIGHT") (pin "S") (pinfunction "S_S") (pintype "passive"))
      (node (ref "RIGHT") (pin "SS") (pinfunction "SS_SS") (pintype "passive"))
    )
    (net (code "54") (name "Net-(C3-Pad1)") (class "Default")
      (node (ref "C3") (pin "1") (pinfunction "1_1") (pintype "passive"))
      (node (ref "IC1") (pin "7") (pinfunction "7_7") (pintype "passive"))
    )
    (net (code "55") (name "Net-(C3-Pad2)") (class "Default")
      (node (ref "C3") (pin "2") (pinfunction "2_2") (pintype "passive"))
      (node (ref "IC1") (pin "8") (pinfunction "8_8") (pintype "passive"))
      (node (ref "LEFT") (pin "2") (pinfunction "2_2") (pintype "passive"))
      (node (ref "LEFT") (pin "T") (pinfunction "T_T") (pintype "passive"))
    )
    (net (code "56") (name "Net-(C4-Pad1)") (class "Default")
      (node (ref "C4") (pin "1") (pinfunction "1_1") (pintype "passive"))
      (node (ref "IC1") (pin "2") (pinfunction "2_2") (pintype "passive"))
    )
    (net (code "57") (name "Net-(C4-Pad2)") (class "Default")
      (node (ref "C4") (pin "2") (pinfunction "2_2") (pintype "passive"))
      (node (ref "IC1") (pin "1") (pinfunction "1_1") (pintype "passive"))
      (node (ref "LEFT") (pin "3") (pinfunction "3_3") (pintype "passive"))
      (node (ref "LEFT") (pin "R") (pinfunction "R_R") (pintype "passive"))
    )
    (net (code "58") (name "Net-(C7-Pad1)") (class "Default")
      (node (ref "C7") (pin "1") (pinfunction "1_1") (pintype "passive"))
      (node (ref "IC2") (pin "7") (pinfunction "7_7") (pintype "passive"))
    )
    (net (code "59") (name "Net-(C7-Pad2)") (class "Default")
      (node (ref "C7") (pin "2") (pinfunction "2_2") (pintype "passive"))
      (node (ref "IC2") (pin "8") (pinfunction "8_8") (pintype "passive"))
      (node (ref "RIGHT") (pin "2") (pinfunction "2_2") (pintype "passive"))
      (node (ref "RIGHT") (pin "T") (pinfunction "T_T") (pintype "passive"))
    )
    (net (code "60") (name "Net-(C8-Pad1)") (class "Default")
      (node (ref "C8") (pin "1") (pinfunction "1_1") (pintype "passive"))
      (node (ref "IC2") (pin "2") (pinfunction "2_2") (pintype "passive"))
    )
    (net (code "61") (name "Net-(C8-Pad2)") (class "Default")
      (node (ref "C8") (pin "2") (pinfunction "2_2") (pintype "passive"))
      (node (ref "IC2") (pin "1") (pinfunction "1_1") (pintype "passive"))
      (node (ref "RIGHT") (pin "3") (pinfunction "3_3") (pintype "passive"))
      (node (ref "RIGHT") (pin "R") (pinfunction "R_R") (pintype "passive"))
    )
    (net (code "62") (name "Net-(C9-Pad1)") (class "Default")
      (node (ref "C9") (pin "1") (pinfunction "1_1") (pintype "passive"))
      (node (ref "IC2") (pin "4") (pinfunction "4_4") (pintype "passive"))
    )
    (net (code "63") (name "Net-(C10-Pad1)") (class "Default")
      (node (ref "C10") (pin "1") (pinfunction "1_1") (pintype "passive"))
      (node (ref "IC1") (pin "4") (pinfunction "4_4") (pintype "passive"))
    )
    (net (code "64") (name "Net-(C300-Pad1)") (class "Default")
      (node (ref "C300") (pin "1") (pinfunction "1_1") (pintype "passive"))
      (node (ref "R502") (pin "1") (pinfunction "1_1") (pintype "passive"))
      (node (ref "R8") (pin "2") (pinfunction "2_2") (pintype "passive"))
    )
    (net (code "65") (name "Net-(C300-Pad2)") (class "Default")
      (node (ref "C300") (pin "2") (pinfunction "2_2") (pintype "passive"))
      (node (ref "J4") (pin "T") (pinfunction "T_T") (pintype "passive"))
      (node (ref "J5") (pin "TN") (pinfunction "TN_TN") (pintype "passive"))
      (node (ref "R300") (pin "2") (pinfunction "2_2") (pintype "passive"))
    )
    (net (code "66") (name "Net-(C301-Pad1)") (class "Default")
      (node (ref "C301") (pin "1") (pinfunction "1_1") (pintype "passive"))
      (node (ref "R507") (pin "1") (pinfunction "1_1") (pintype "passive"))
      (node (ref "R9") (pin "2") (pinfunction "2_2") (pintype "passive"))
    )
    (net (code "67") (name "Net-(IC3-ADJ)") (class "Default")
      (node (ref "C18") (pin "+") (pinfunction "+_+") (pintype "passive"))
      (node (ref "IC3") (pin "1") (pinfunction "ADJ_1") (pintype "input"))
      (node (ref "R6") (pin "2") (pinfunction "2_2") (pintype "passive"))
      (node (ref "R7") (pin "1") (pinfunction "1_1") (pintype "passive"))
    )
    (net (code "68") (name "Net-(IC5A-+IN)") (class "Default")
      (node (ref "IC5") (pin "3") (pinfunction "+IN_3") (pintype "input"))
      (node (ref "R504") (pin "2") (pinfunction "2_2") (pintype "passive"))
      (node (ref "R505") (pin "1") (pinfunction "1_1") (pintype "passive"))
    )
    (net (code "69") (name "Net-(IC5A--IN)") (class "Default")
      (node (ref "IC5") (pin "2") (pinfunction "-IN_2") (pintype "input"))
      (node (ref "R501") (pin "1") (pinfunction "1_1") (pintype "passive"))
      (node (ref "R502") (pin "2") (pinfunction "2_2") (pintype "passive"))
    )
    (net (code "70") (name "Net-(IC5A-OUT)") (class "Default")
      (node (ref "IC5") (pin "1") (pinfunction "OUT_1") (pintype "output"))
      (node (ref "R501") (pin "2") (pinfunction "2_2") (pintype "passive"))
      (node (ref "R503") (pin "1") (pinfunction "1_1") (pintype "passive"))
    )
    (net (code "71") (name "Net-(IC5B-+IN)") (class "Default")
      (node (ref "IC5") (pin "5") (pinfunction "+IN_5") (pintype "input"))
      (node (ref "R509") (pin "2") (pinfunction "2_2") (pintype "passive"))
      (node (ref "R510") (pin "1") (pinfunction "1_1") (pintype "passive"))
    )
    (net (code "72") (name "Net-(IC5B--IN)") (class "Default")
      (node (ref "IC5") (pin "6") (pinfunction "-IN_6") (pintype "input"))
      (node (ref "R506") (pin "1") (pinfunction "1_1") (pintype "passive"))
      (node (ref "R507") (pin "2") (pinfunction "2_2") (pintype "passive"))
    )
    (net (code "73") (name "Net-(IC5B-OUT)") (class "Default")
      (node (ref "IC5") (pin "7") (pinfunction "OUT_7") (pintype "output"))
      (node (ref "R506") (pin "2") (pinfunction "2_2") (pintype "passive"))
      (node (ref "R508") (pin "1") (pinfunction "1_1") (pintype "passive"))
    )
    (net (code "74") (name "VCC{slash}2") (class "Default")
      (node (ref "VMID") (pin "1") (pinfunction "1_1") (pintype "passive"))
    )
    (net (code "75") (name "unconnected-(J4-PadR)") (class "Default")
      (node (ref "J4") (pin "R") (pinfunction "R_R") (pintype "passive"))
    )
    (net (code "76") (name "unconnected-(J4-PadRN)") (class "Default")
      (node (ref "J4") (pin "RN") (pinfunction "RN_RN") (pintype "passive"))
    )
    (net (code "77") (name "unconnected-(J4-PadSN)") (class "Default")
      (node (ref "J4") (pin "SN") (pinfunction "SN_SN") (pintype "passive"))
    )
    (net (code "78") (name "unconnected-(J5-PadR)") (class "Default")
      (node (ref "J5") (pin "R") (pinfunction "R_R") (pintype "passive"))
    )
    (net (code "79") (name "unconnected-(J5-PadRN)") (class "Default")
      (node (ref "J5") (pin "RN") (pinfunction "RN_RN") (pintype "passive"))
    )
    (net (code "80") (name "unconnected-(J5-PadSN)") (class "Default")
      (node (ref "J5") (pin "SN") (pinfunction "SN_SN") (pintype "passive"))
    )
    (net (code "81") (name "unconnected-(JP1-Pad1)") (class "Default")
      (node (ref "JP1") (pin "1") (pinfunction "1_1") (pintype "passive"))
    )
    (net (code "82") (name "unconnected-(JP1-Pad4)") (class "Default")
      (node (ref "JP1") (pin "4") (pinfunction "4_4") (pintype "passive"))
    )
    (net (code "83") (name "unconnected-(JP1-Pad5)") (class "Default")
      (node (ref "JP1") (pin "5") (pinfunction "5_5") (pintype "passive"))
    )
    (net (code "84") (name "unconnected-(JP3-Pad3)") (class "Default")
      (node (ref "JP3") (pin "3") (pinfunction "3_3") (pintype "passive"))
    )
    (net (code "85") (name "unconnected-(JP5-Pad3)") (class "Default")
      (node (ref "JP5") (pin "3") (pinfunction "3_3") (pintype "passive"))
    )
    (net (code "86") (name "unconnected-(JP13-Pad1)") (class "Default")
      (node (ref "JP13") (pin "1") (pinfunction "1_1") (pintype "passive"))
    )
    (net (code "87") (name "unconnected-(JP13-Pad4)") (class "Default")
      (node (ref "JP13") (pin "4") (pinfunction "4_4") (pintype "passive"))
    )
    (net (code "88") (name "unconnected-(JP13-Pad5)") (class "Default")
      (node (ref "JP13") (pin "5") (pinfunction "5_5") (pintype "passive"))
    )
    (net (code "89") (name "unconnected-(LEFT-PadRS)") (class "Default")
      (node (ref "LEFT") (pin "RS") (pinfunction "RS_RS") (pintype "passive"))
    )
    (net (code "90") (name "unconnected-(LEFT-PadTS)") (class "Default")
      (node (ref "LEFT") (pin "TS") (pinfunction "TS_TS") (pintype "passive"))
    )
    (net (code "91") (name "unconnected-(RIGHT-PadRS)") (class "Default")
      (node (ref "RIGHT") (pin "RS") (pinfunction "RS_RS") (pintype "passive"))
    )
    (net (code "92") (name "unconnected-(RIGHT-PadTS)") (class "Default")
      (node (ref "RIGHT") (pin "TS") (pinfunction "TS_TS") (pintype "passive"))
    )
    (net (code "93") (name "unconnected-(USB-Pad4)") (class "Default")
      (node (ref "USB") (pin "4") (pinfunction "4_4") (pintype "passive"))
    )
    (net (code "94") (name "unconnected-(USB1-Pad4)") (class "Default")
      (node (ref "USB1") (pin "4") (pinfunction "4_4") (pintype "passive"))
    )
  )
)
